# Conn2_1.net
KiCad netlist of a schematic drawn in Altium Designer
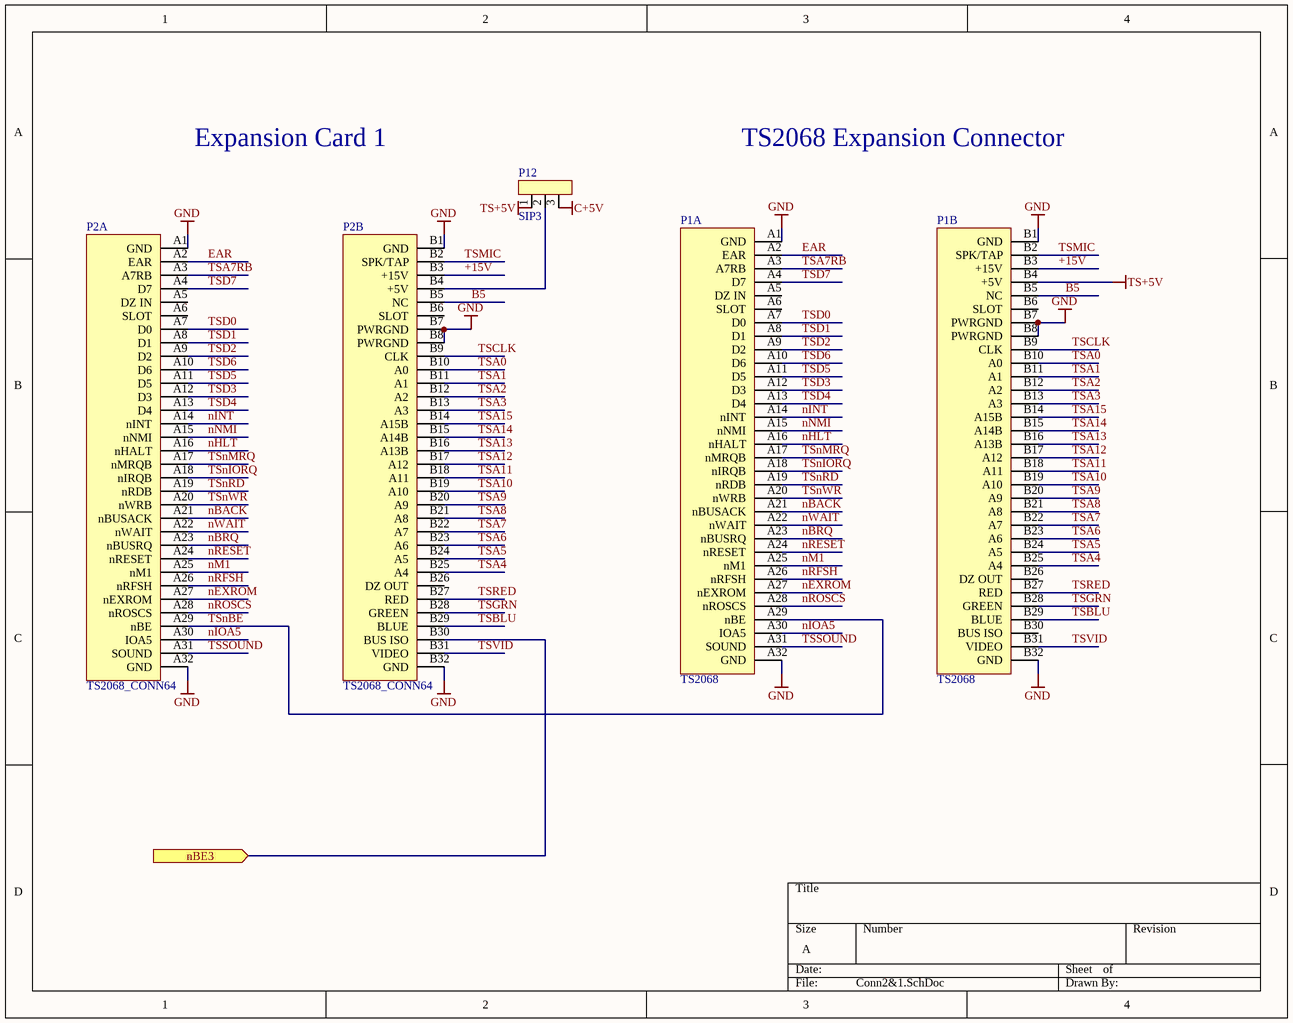
[diagram p0: Conn2&1.SchDoc]

(export (version "E")
  (design (tool "Eeschema 10.0.6"))
  (components
    (comp (ref "P1") (value "TS2068") (footprint "TS2068") (libsource (lib "Modules") (part "TS2068")))
    (comp (ref "P2")
      (value "TS2068_CONN64")
      (footprint "64CARDEDGE")
      (description "64 Position Female Connector Non Specified - Dual Edge Gold 0.100\" (2.54mm) Black")
      (fields (field (name "MFG") "TD"))
      (libsource (lib "Connectors") (part "TS2068_CONN64"))
    )
    (comp (ref "P12") (value "SIP3") (footprint "SIP3") (libsource (lib "Connectors") (part "SIP3")))
  )
  (nets
    (net (code "1") (name "/+15V") (class "Default")
      (node (ref "P1") (pin "B3") (pinfunction "+15V_B3") (pintype "passive"))
      (node (ref "P2") (pin "B3") (pinfunction "+15V_B3") (pintype "passive"))
    )
    (net (code "2") (name "/B5") (class "Default")
      (node (ref "P1") (pin "B5") (pinfunction "NC_B5") (pintype "passive"))
      (node (ref "P2") (pin "B5") (pinfunction "NC_B5") (pintype "passive"))
    )
    (net (code "3") (name "/EAR") (class "Default")
      (node (ref "P1") (pin "A2") (pinfunction "EAR_A2") (pintype "passive"))
      (node (ref "P2") (pin "A2") (pinfunction "EAR_A2") (pintype "passive"))
    )
    (net (code "4") (name "/TSA0") (class "Default")
      (node (ref "P1") (pin "B10") (pinfunction "A0_B10") (pintype "passive"))
      (node (ref "P2") (pin "B10") (pinfunction "A0_B10") (pintype "passive"))
    )
    (net (code "5") (name "/TSA1") (class "Default")
      (node (ref "P1") (pin "B11") (pinfunction "A1_B11") (pintype "passive"))
      (node (ref "P2") (pin "B11") (pinfunction "A1_B11") (pintype "passive"))
    )
    (net (code "6") (name "/TSA2") (class "Default")
      (node (ref "P1") (pin "B12") (pinfunction "A2_B12") (pintype "passive"))
      (node (ref "P2") (pin "B12") (pinfunction "A2_B12") (pintype "passive"))
    )
    (net (code "7") (name "/TSA3") (class "Default")
      (node (ref "P1") (pin "B13") (pinfunction "A3_B13") (pintype "passive"))
      (node (ref "P2") (pin "B13") (pinfunction "A3_B13") (pintype "passive"))
    )
    (net (code "8") (name "/TSA4") (class "Default")
      (node (ref "P1") (pin "B25") (pinfunction "A4_B25") (pintype "passive"))
      (node (ref "P2") (pin "B25") (pinfunction "A4_B25") (pintype "passive"))
    )
    (net (code "9") (name "/TSA5") (class "Default")
      (node (ref "P1") (pin "B24") (pinfunction "A5_B24") (pintype "passive"))
      (node (ref "P2") (pin "B24") (pinfunction "A5_B24") (pintype "passive"))
    )
    (net (code "10") (name "/TSA6") (class "Default")
      (node (ref "P1") (pin "B23") (pinfunction "A6_B23") (pintype "passive"))
      (node (ref "P2") (pin "B23") (pinfunction "A6_B23") (pintype "passive"))
    )
    (net (code "11") (name "/TSA7") (class "Default")
      (node (ref "P1") (pin "B22") (pinfunction "A7_B22") (pintype "passive"))
      (node (ref "P2") (pin "B22") (pinfunction "A7_B22") (pintype "passive"))
    )
    (net (code "12") (name "/TSA7RB") (class "Default")
      (node (ref "P1") (pin "A3") (pinfunction "A7RB_A3") (pintype "passive"))
      (node (ref "P2") (pin "A3") (pinfunction "A7RB_A3") (pintype "passive"))
    )
    (net (code "13") (name "/TSA8") (class "Default")
      (node (ref "P1") (pin "B21") (pinfunction "A8_B21") (pintype "passive"))
      (node (ref "P2") (pin "B21") (pinfunction "A8_B21") (pintype "passive"))
    )
    (net (code "14") (name "/TSA9") (class "Default")
      (node (ref "P1") (pin "B20") (pinfunction "A9_B20") (pintype "passive"))
      (node (ref "P2") (pin "B20") (pinfunction "A9_B20") (pintype "passive"))
    )
    (net (code "15") (name "/TSA10") (class "Default")
      (node (ref "P1") (pin "B19") (pinfunction "A10_B19") (pintype "passive"))
      (node (ref "P2") (pin "B19") (pinfunction "A10_B19") (pintype "passive"))
    )
    (net (code "16") (name "/TSA11") (class "Default")
      (node (ref "P1") (pin "B18") (pinfunction "A11_B18") (pintype "passive"))
      (node (ref "P2") (pin "B18") (pinfunction "A11_B18") (pintype "passive"))
    )
    (net (code "17") (name "/TSA12") (class "Default")
      (node (ref "P1") (pin "B17") (pinfunction "A12_B17") (pintype "passive"))
      (node (ref "P2") (pin "B17") (pinfunction "A12_B17") (pintype "passive"))
    )
    (net (code "18") (name "/TSA13") (class "Default")
      (node (ref "P1") (pin "B16") (pinfunction "A13B_B16") (pintype "passive"))
      (node (ref "P2") (pin "B16") (pinfunction "A13B_B16") (pintype "passive"))
    )
    (net (code "19") (name "/TSA14") (class "Default")
      (node (ref "P1") (pin "B15") (pinfunction "A14B_B15") (pintype "passive"))
      (node (ref "P2") (pin "B15") (pinfunction "A14B_B15") (pintype "passive"))
    )
    (net (code "20") (name "/TSA15") (class "Default")
      (node (ref "P1") (pin "B14") (pinfunction "A15B_B14") (pintype "passive"))
      (node (ref "P2") (pin "B14") (pinfunction "A15B_B14") (pintype "passive"))
    )
    (net (code "21") (name "/TSBLU") (class "Default")
      (node (ref "P1") (pin "B29") (pinfunction "BLUE_B29") (pintype "passive"))
      (node (ref "P2") (pin "B29") (pinfunction "BLUE_B29") (pintype "passive"))
    )
    (net (code "22") (name "/TSCLK") (class "Default")
      (node (ref "P1") (pin "B9") (pinfunction "CLK_B9") (pintype "passive"))
      (node (ref "P2") (pin "B9") (pinfunction "CLK_B9") (pintype "passive"))
    )
    (net (code "23") (name "/TSD0") (class "Default")
      (node (ref "P1") (pin "A7") (pinfunction "D0_A7") (pintype "passive"))
      (node (ref "P2") (pin "A7") (pinfunction "D0_A7") (pintype "passive"))
    )
    (net (code "24") (name "/TSD1") (class "Default")
      (node (ref "P1") (pin "A8") (pinfunction "D1_A8") (pintype "passive"))
      (node (ref "P2") (pin "A8") (pinfunction "D1_A8") (pintype "passive"))
    )
    (net (code "25") (name "/TSD2") (class "Default")
      (node (ref "P1") (pin "A9") (pinfunction "D2_A9") (pintype "passive"))
      (node (ref "P2") (pin "A9") (pinfunction "D2_A9") (pintype "passive"))
    )
    (net (code "26") (name "/TSD3") (class "Default")
      (node (ref "P1") (pin "A12") (pinfunction "D3_A12") (pintype "passive"))
      (node (ref "P2") (pin "A12") (pinfunction "D3_A12") (pintype "passive"))
    )
    (net (code "27") (name "/TSD4") (class "Default")
      (node (ref "P1") (pin "A13") (pinfunction "D4_A13") (pintype "passive"))
      (node (ref "P2") (pin "A13") (pinfunction "D4_A13") (pintype "passive"))
    )
    (net (code "28") (name "/TSD5") (class "Default")
      (node (ref "P1") (pin "A11") (pinfunction "D5_A11") (pintype "passive"))
      (node (ref "P2") (pin "A11") (pinfunction "D5_A11") (pintype "passive"))
    )
    (net (code "29") (name "/TSD6") (class "Default")
      (node (ref "P1") (pin "A10") (pinfunction "D6_A10") (pintype "passive"))
      (node (ref "P2") (pin "A10") (pinfunction "D6_A10") (pintype "passive"))
    )
    (net (code "30") (name "/TSD7") (class "Default")
      (node (ref "P1") (pin "A4") (pinfunction "D7_A4") (pintype "passive"))
      (node (ref "P2") (pin "A4") (pinfunction "D7_A4") (pintype "passive"))
    )
    (net (code "31") (name "/TSGRN") (class "Default")
      (node (ref "P1") (pin "B28") (pinfunction "GREEN_B28") (pintype "passive"))
      (node (ref "P2") (pin "B28") (pinfunction "GREEN_B28") (pintype "passive"))
    )
    (net (code "32") (name "/TSMIC") (class "Default")
      (node (ref "P1") (pin "B2") (pinfunction "SPK/TAP_B2") (pintype "passive"))
      (node (ref "P2") (pin "B2") (pinfunction "SPK/TAP_B2") (pintype "passive"))
    )
    (net (code "33") (name "/TSRED") (class "Default")
      (node (ref "P1") (pin "B27") (pinfunction "RED_B27") (pintype "passive"))
      (node (ref "P2") (pin "B27") (pinfunction "RED_B27") (pintype "passive"))
    )
    (net (code "34") (name "/TSSOUND") (class "Default")
      (node (ref "P1") (pin "A31") (pinfunction "SOUND_A31") (pintype "passive"))
      (node (ref "P2") (pin "A31") (pinfunction "SOUND_A31") (pintype "passive"))
    )
    (net (code "35") (name "/TSVID") (class "Default")
      (node (ref "P1") (pin "B31") (pinfunction "VIDEO_B31") (pintype "passive"))
      (node (ref "P2") (pin "B31") (pinfunction "VIDEO_B31") (pintype "passive"))
    )
    (net (code "36") (name "/TSnBE") (class "Default")
      (node (ref "P1") (pin "A29") (pinfunction "nBE_A29") (pintype "passive"))
      (node (ref "P2") (pin "A29") (pinfunction "nBE_A29") (pintype "passive"))
    )
    (net (code "37") (name "/TSnIORQ") (class "Default")
      (node (ref "P1") (pin "A18") (pinfunction "nIRQB_A18") (pintype "passive"))
      (node (ref "P2") (pin "A18") (pinfunction "nIRQB_A18") (pintype "passive"))
    )
    (net (code "38") (name "/TSnMRQ") (class "Default")
      (node (ref "P1") (pin "A17") (pinfunction "nMRQB_A17") (pintype "passive"))
      (node (ref "P2") (pin "A17") (pinfunction "nMRQB_A17") (pintype "passive"))
    )
    (net (code "39") (name "/TSnRD") (class "Default")
      (node (ref "P1") (pin "A19") (pinfunction "nRDB_A19") (pintype "passive"))
      (node (ref "P2") (pin "A19") (pinfunction "nRDB_A19") (pintype "passive"))
    )
    (net (code "40") (name "/TSnWR") (class "Default")
      (node (ref "P1") (pin "A20") (pinfunction "nWRB_A20") (pintype "passive"))
      (node (ref "P2") (pin "A20") (pinfunction "nWRB_A20") (pintype "passive"))
    )
    (net (code "41") (name "/nBACK") (class "Default")
      (node (ref "P1") (pin "A21") (pinfunction "nBUSACK_A21") (pintype "passive"))
      (node (ref "P2") (pin "A21") (pinfunction "nBUSACK_A21") (pintype "passive"))
    )
    (net (code "42") (name "/nBE3") (class "Default")
      (node (ref "P2") (pin "B30") (pinfunction "BUS_ISO_B30") (pintype "passive"))
    )
    (net (code "43") (name "/nBRQ") (class "Default")
      (node (ref "P1") (pin "A23") (pinfunction "nBUSRQ_A23") (pintype "passive"))
      (node (ref "P2") (pin "A23") (pinfunction "nBUSRQ_A23") (pintype "passive"))
    )
    (net (code "44") (name "/nEXROM") (class "Default")
      (node (ref "P1") (pin "A27") (pinfunction "nEXROM_A27") (pintype "passive"))
      (node (ref "P2") (pin "A27") (pinfunction "nEXROM_A27") (pintype "passive"))
    )
    (net (code "45") (name "/nHLT") (class "Default")
      (node (ref "P1") (pin "A16") (pinfunction "nHALT_A16") (pintype "passive"))
      (node (ref "P2") (pin "A16") (pinfunction "nHALT_A16") (pintype "passive"))
    )
    (net (code "46") (name "/nINT") (class "Default")
      (node (ref "P1") (pin "A14") (pinfunction "nINT_A14") (pintype "passive"))
      (node (ref "P2") (pin "A14") (pinfunction "nINT_A14") (pintype "passive"))
    )
    (net (code "47") (name "/nIOA5") (class "Default")
      (node (ref "P1") (pin "A30") (pinfunction "IOA5_A30") (pintype "passive"))
      (node (ref "P2") (pin "A30") (pinfunction "IOA5_A30") (pintype "passive"))
    )
    (net (code "48") (name "/nM1") (class "Default")
      (node (ref "P1") (pin "A25") (pinfunction "nM1_A25") (pintype "passive"))
      (node (ref "P2") (pin "A25") (pinfunction "nM1_A25") (pintype "passive"))
    )
    (net (code "49") (name "/nNMI") (class "Default")
      (node (ref "P1") (pin "A15") (pinfunction "nNMI_A15") (pintype "passive"))
      (node (ref "P2") (pin "A15") (pinfunction "nNMI_A15") (pintype "passive"))
    )
    (net (code "50") (name "/nRESET") (class "Default")
      (node (ref "P1") (pin "A24") (pinfunction "nRESET_A24") (pintype "passive"))
      (node (ref "P2") (pin "A24") (pinfunction "nRESET_A24") (pintype "passive"))
    )
    (net (code "51") (name "/nRFSH") (class "Default")
      (node (ref "P1") (pin "A26") (pinfunction "nRFSH_A26") (pintype "passive"))
      (node (ref "P2") (pin "A26") (pinfunction "nRFSH_A26") (pintype "passive"))
    )
    (net (code "52") (name "/nROSCS") (class "Default")
      (node (ref "P1") (pin "A28") (pinfunction "nROSCS_A28") (pintype "passive"))
      (node (ref "P2") (pin "A28") (pinfunction "nROSCS_A28") (pintype "passive"))
    )
    (net (code "53") (name "/nWAIT") (class "Default")
      (node (ref "P1") (pin "A22") (pinfunction "nWAIT_A22") (pintype "passive"))
      (node (ref "P2") (pin "A22") (pinfunction "nWAIT_A22") (pintype "passive"))
    )
    (net (code "54") (name "C+5V") (class "Default") (node (ref "P12") (pin "3") (pintype "passive")))
    (net (code "55") (name "GND") (class "Default")
      (node (ref "P1") (pin "A1") (pinfunction "GND_A1") (pintype "passive"))
      (node (ref "P1") (pin "A32") (pinfunction "GND_A32") (pintype "passive"))
      (node (ref "P1") (pin "B1") (pinfunction "GND_B1") (pintype "passive"))
      (node (ref "P1") (pin "B32") (pinfunction "GND_B32") (pintype "passive"))
      (node (ref "P1") (pin "B7") (pinfunction "PWRGND_B7") (pintype "passive"))
      (node (ref "P1") (pin "B8") (pinfunction "PWRGND_B8") (pintype "passive"))
      (node (ref "P2") (pin "A1") (pinfunction "GND_A1") (pintype "passive"))
      (node (ref "P2") (pin "A32") (pinfunction "GND_A32") (pintype "passive"))
      (node (ref "P2") (pin "B1") (pinfunction "GND_B1") (pintype "passive"))
      (node (ref "P2") (pin "B32") (pinfunction "GND_B32") (pintype "passive"))
      (node (ref "P2") (pin "B7") (pinfunction "PWRGND_B7") (pintype "passive"))
      (node (ref "P2") (pin "B8") (pinfunction "PWRGND_B8") (pintype "passive"))
    )
    (net (code "56") (name "Net-(P2B-+5V)") (class "Default")
      (node (ref "P12") (pin "2") (pintype "passive"))
      (node (ref "P2") (pin "B4") (pinfunction "+5V_B4") (pintype "passive"))
    )
    (net (code "57") (name "TS+5V") (class "Default")
      (node (ref "P1") (pin "B4") (pinfunction "+5V_B4") (pintype "passive"))
      (node (ref "P12") (pin "1") (pintype "passive"))
    )
    (net (code "58") (name "unconnected-(P1A-DZ_IN-PadA5)") (class "Default")
      (node (ref "P1") (pin "A5") (pinfunction "DZ_IN_A5") (pintype "passive"))
    )
    (net (code "59") (name "unconnected-(P1A-SLOT-PadA6)") (class "Default")
      (node (ref "P1") (pin "A6") (pinfunction "SLOT_A6") (pintype "passive"))
    )
    (net (code "60") (name "unconnected-(P1B-BUS_ISO-PadB30)") (class "Default")
      (node (ref "P1") (pin "B30") (pinfunction "BUS_ISO_B30") (pintype "passive"))
    )
    (net (code "61") (name "unconnected-(P1B-DZ_OUT-PadB26)") (class "Default")
      (node (ref "P1") (pin "B26") (pinfunction "DZ_OUT_B26") (pintype "passive"))
    )
    (net (code "62") (name "unconnected-(P1B-SLOT-PadB6)") (class "Default")
      (node (ref "P1") (pin "B6") (pinfunction "SLOT_B6") (pintype "passive"))
    )
    (net (code "63") (name "unconnected-(P2A-DZ_IN-PadA5)") (class "Default")
      (node (ref "P2") (pin "A5") (pinfunction "DZ_IN_A5") (pintype "passive"))
    )
    (net (code "64") (name "unconnected-(P2A-SLOT-PadA6)") (class "Default")
      (node (ref "P2") (pin "A6") (pinfunction "SLOT_A6") (pintype "passive"))
    )
    (net (code "65") (name "unconnected-(P2B-DZ_OUT-PadB26)") (class "Default")
      (node (ref "P2") (pin "B26") (pinfunction "DZ_OUT_B26") (pintype "passive"))
    )
    (net (code "66") (name "unconnected-(P2B-SLOT-PadB6)") (class "Default")
      (node (ref "P2") (pin "B6") (pinfunction "SLOT_B6") (pintype "passive"))
    )
  )
)
